# DS214SD.net
KiCad netlist of a schematic drawn in Altium Designer
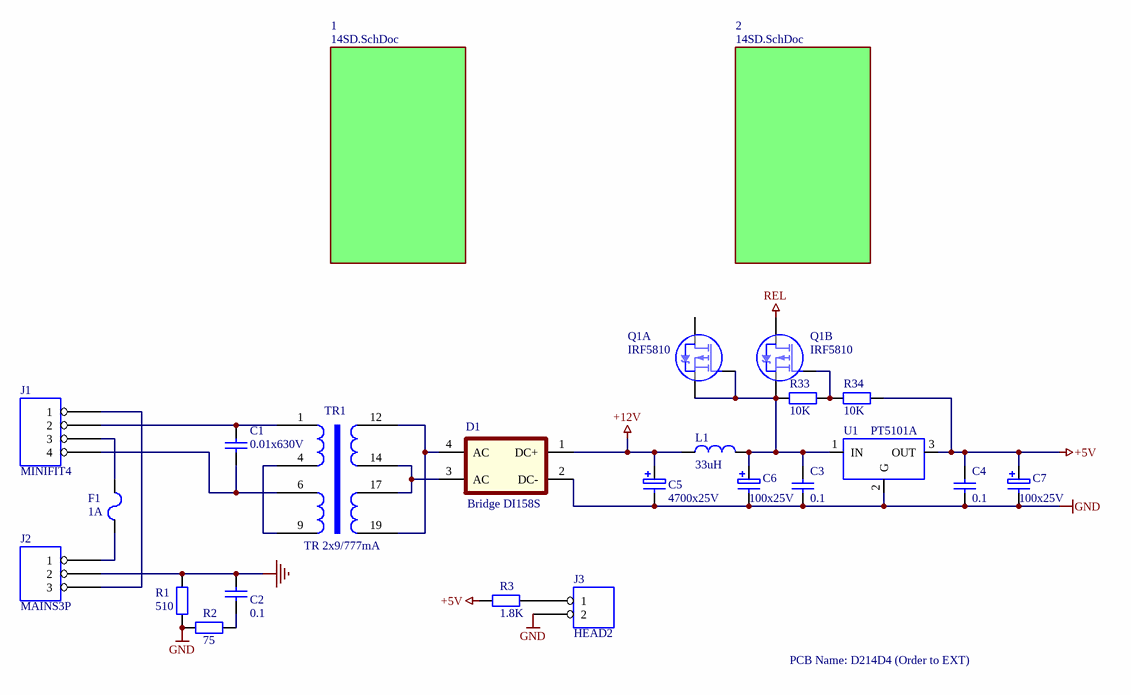
[diagram p0: DS214SD.SchDoc]

(export (version "E")
  (design (tool "Eeschema 10.0.6"))
  (components
    (comp (ref "C1")
      (value "0.01x630V")
      (footprint "C100N")
      (description "Capacitor")
      (fields (field (name "MANUFACTURER") "Generic Components") (field (name "PUBLISHER") "Altium Limited"))
      (libsource (lib "LES") (part "Cap"))
    )
    (comp (ref "C2")
      (value "0.1")
      (footprint "C0805")
      (description "Capacitor")
      (fields (field (name "MANUFACTURER") "Generic Components") (field (name "PUBLISHER") "Altium Limited"))
      (libsource (lib "LES") (part "Cap"))
    )
    (comp (ref "C3")
      (value "0.1")
      (footprint "C0805")
      (description "Capacitor")
      (fields (field (name "MANUFACTURER") "Generic Components") (field (name "PUBLISHER") "Altium Limited"))
      (libsource (lib "LES") (part "Cap"))
    )
    (comp (ref "C4")
      (value "0.1")
      (footprint "C0805")
      (description "Capacitor")
      (fields (field (name "MANUFACTURER") "Generic Components") (field (name "PUBLISHER") "Altium Limited"))
      (libsource (lib "LES") (part "Cap"))
    )
    (comp (ref "C5")
      (value "4700x25V")
      (footprint "CPOL75L")
      (description "Polarized Capacitor (Radial)")
      (fields (field (name "MANUFACTURER") "Generic Components") (field (name "PUBLISHER") "Altium Limited"))
      (libsource (lib "LES") (part "Cap Pol"))
    )
    (comp (ref "C6")
      (value "100x25V")
      (footprint "CPOL25")
      (description "Polarized Capacitor (Radial)")
      (fields (field (name "MANUFACTURER") "Generic Components") (field (name "PUBLISHER") "Altium Limited"))
      (libsource (lib "LES") (part "Cap Pol"))
    )
    (comp (ref "C7")
      (value "100x25V")
      (footprint "CPOL25")
      (description "Polarized Capacitor (Radial)")
      (fields (field (name "MANUFACTURER") "Generic Components") (field (name "PUBLISHER") "Altium Limited"))
      (libsource (lib "LES") (part "Cap Pol"))
    )
    (comp (ref "D1")
      (value "Bridge DI158S")
      (footprint "SDIP")
      (libsource (lib "LES") (part "Bridge DI158S"))
    )
    (comp (ref "F1")
      (value "1A")
      (footprint "FUSE")
      (description "Fuse")
      (libsource (lib "LES") (part "Fuse"))
    )
    (comp (ref "J1") (value "MINIFIT4") (footprint "MINIFIT4") (libsource (lib "LES") (part "HEAD4")))
    (comp (ref "J2") (value "MAINS3P") (footprint "MAINS3P") (libsource (lib "LES") (part "HEAD3")))
    (comp (ref "J3") (value "HEAD2") (footprint "2SIP100") (libsource (lib "LES") (part "HEAD2")))
    (comp (ref "L1") (value "33uH") (footprint "L050") (libsource (lib "LES") (part "INDUCTOR")))
    (comp (ref "Q1")
      (value "IRF5810")
      (footprint "TSOP6")
      (description "P-Channel MOSFET")
      (fields (field (name "PUBLISHER") "Altium Limited"))
      (libsource (lib "LES") (part "IRF5810"))
    )
    (comp (ref "R1")
      (value "510")
      (footprint "R0805")
      (description "Resistor")
      (fields (field (name "MANUFACTURER") "Generic Components") (field (name "PUBLISHER") "Altium Limited"))
      (libsource (lib "") (part "Res_1"))
    )
    (comp (ref "R2")
      (value "75")
      (footprint "R0805")
      (description "Resistor")
      (fields (field (name "MANUFACTURER") "Generic Components") (field (name "PUBLISHER") "Altium Limited"))
      (libsource (lib "LES") (part "Res"))
    )
    (comp (ref "R3")
      (value "1.8K")
      (footprint "R0805")
      (description "Resistor")
      (fields (field (name "MANUFACTURER") "Generic Components") (field (name "PUBLISHER") "Altium Limited"))
      (libsource (lib "LES") (part "Res"))
    )
    (comp (ref "R33")
      (value "10K")
      (footprint "R0805")
      (description "Resistor")
      (fields (field (name "MANUFACTURER") "Generic Components") (field (name "PUBLISHER") "Altium Limited"))
      (libsource (lib "LES") (part "Res"))
    )
    (comp (ref "R34")
      (value "10K")
      (footprint "R0805")
      (description "Resistor")
      (fields (field (name "MANUFACTURER") "Generic Components") (field (name "PUBLISHER") "Altium Limited"))
      (libsource (lib "LES") (part "Res"))
    )
    (comp (ref "TR1")
      (value "TR 2x9/777mA")
      (footprint "TR14VA")
      (libsource (lib "LES") (part "TR 2x9/777mA"))
    )
    (comp (ref "U1") (value "PT5101A") (footprint "PT5101A-LOW") (libsource (lib "LES") (part "PT5101A")))
  )
  (nets
    (net (code "1") (name "+5V") (class "Default")
      (node (ref "C4") (pin "2") (pinfunction "2_2") (pintype "passive"))
      (node (ref "C7") (pin "1") (pinfunction "1_1") (pintype "passive"))
      (node (ref "R3") (pin "1") (pinfunction "1_1") (pintype "passive"))
      (node (ref "R34") (pin "2") (pinfunction "2_2") (pintype "passive"))
      (node (ref "U1") (pin "3") (pinfunction "OUT_3") (pintype "passive"))
    )
    (net (code "2") (name "+12V") (class "Default")
      (node (ref "C5") (pin "1") (pinfunction "1_1") (pintype "passive"))
      (node (ref "D1") (pin "1") (pinfunction "DC+_1") (pintype "passive"))
      (node (ref "L1") (pin "1") (pinfunction "1_1") (pintype "passive"))
    )
    (net (code "3") (name "GND") (class "Default")
      (node (ref "C3") (pin "1") (pinfunction "1_1") (pintype "passive"))
      (node (ref "C4") (pin "1") (pinfunction "1_1") (pintype "passive"))
      (node (ref "C5") (pin "2") (pinfunction "2_2") (pintype "passive"))
      (node (ref "C6") (pin "2") (pinfunction "2_2") (pintype "passive"))
      (node (ref "C7") (pin "2") (pinfunction "2_2") (pintype "passive"))
      (node (ref "D1") (pin "2") (pinfunction "DC-_2") (pintype "passive"))
      (node (ref "J3") (pin "2") (pinfunction "2_2") (pintype "passive"))
      (node (ref "R1") (pin "1") (pinfunction "1_1") (pintype "passive"))
      (node (ref "R2") (pin "1") (pinfunction "1_1") (pintype "passive"))
      (node (ref "U1") (pin "2") (pinfunction "G_2") (pintype "passive"))
    )
    (net (code "4") (name "GNE") (class "Default")
      (node (ref "C2") (pin "2") (pinfunction "2_2") (pintype "passive"))
      (node (ref "J2") (pin "2") (pinfunction "2_2") (pintype "passive"))
      (node (ref "R1") (pin "2") (pinfunction "2_2") (pintype "passive"))
    )
    (net (code "5") (name "Net-(C1-Pad1)") (class "Default")
      (node (ref "C1") (pin "1") (pinfunction "1_1") (pintype "passive"))
      (node (ref "J1") (pin "4") (pinfunction "4_4") (pintype "passive"))
      (node (ref "TR1") (pin "6") (pinfunction "6_6") (pintype "passive"))
    )
    (net (code "6") (name "Net-(C1-Pad2)") (class "Default")
      (node (ref "C1") (pin "2") (pinfunction "2_2") (pintype "passive"))
      (node (ref "J1") (pin "2") (pinfunction "2_2") (pintype "passive"))
      (node (ref "TR1") (pin "1") (pinfunction "1_1") (pintype "passive"))
    )
    (net (code "7") (name "Net-(C2-Pad1)") (class "Default")
      (node (ref "C2") (pin "1") (pinfunction "1_1") (pintype "passive"))
      (node (ref "R2") (pin "2") (pinfunction "2_2") (pintype "passive"))
    )
    (net (code "8") (name "Net-(D1-AC-Pad3)") (class "Default")
      (node (ref "D1") (pin "3") (pinfunction "AC_3") (pintype "passive"))
      (node (ref "TR1") (pin "14") (pinfunction "14_14") (pintype "passive"))
      (node (ref "TR1") (pin "17") (pinfunction "17_17") (pintype "passive"))
    )
    (net (code "9") (name "Net-(D1-AC-Pad4)") (class "Default")
      (node (ref "D1") (pin "4") (pinfunction "AC_4") (pintype "passive"))
      (node (ref "TR1") (pin "12") (pinfunction "12_12") (pintype "passive"))
      (node (ref "TR1") (pin "19") (pinfunction "19_19") (pintype "passive"))
    )
    (net (code "10") (name "Net-(F1-Pad1)") (class "Default")
      (node (ref "F1") (pin "1") (pinfunction "1_1") (pintype "passive"))
      (node (ref "J2") (pin "1") (pinfunction "1_1") (pintype "passive"))
    )
    (net (code "11") (name "Net-(F1-Pad2)") (class "Default")
      (node (ref "F1") (pin "2") (pinfunction "2_2") (pintype "passive"))
      (node (ref "J1") (pin "3") (pinfunction "3_3") (pintype "passive"))
    )
    (net (code "12") (name "Net-(J1-Pad1)") (class "Default")
      (node (ref "J1") (pin "1") (pinfunction "1_1") (pintype "passive"))
      (node (ref "J2") (pin "3") (pinfunction "3_3") (pintype "passive"))
    )
    (net (code "13") (name "Net-(J3-Pad1)") (class "Default")
      (node (ref "J3") (pin "1") (pinfunction "1_1") (pintype "passive"))
      (node (ref "R3") (pin "2") (pinfunction "2_2") (pintype "passive"))
    )
    (net (code "14") (name "Net-(Q1A-G1)") (class "Default")
      (node (ref "C3") (pin "2") (pinfunction "2_2") (pintype "passive"))
      (node (ref "C6") (pin "1") (pinfunction "1_1") (pintype "passive"))
      (node (ref "L1") (pin "2") (pinfunction "2_2") (pintype "passive"))
      (node (ref "Q1") (pin "1") (pinfunction "G1_1") (pintype "passive"))
      (node (ref "Q1") (pin "2") (pinfunction "S2_2") (pintype "passive"))
      (node (ref "Q1") (pin "5") (pinfunction "S1_5") (pintype "passive"))
      (node (ref "R33") (pin "1") (pinfunction "1_1") (pintype "passive"))
      (node (ref "U1") (pin "1") (pinfunction "IN_1") (pintype "passive"))
    )
    (net (code "15") (name "Net-(Q1B-G2)") (class "Default")
      (node (ref "Q1") (pin "3") (pinfunction "G2_3") (pintype "passive"))
      (node (ref "R33") (pin "2") (pinfunction "2_2") (pintype "passive"))
      (node (ref "R34") (pin "1") (pinfunction "1_1") (pintype "passive"))
    )
    (net (code "16") (name "Net-(TR1-Pad4)") (class "Default")
      (node (ref "TR1") (pin "4") (pinfunction "4_4") (pintype "passive"))
      (node (ref "TR1") (pin "9") (pinfunction "9_9") (pintype "passive"))
    )
    (net (code "17") (name "REL") (class "Default")
      (node (ref "Q1") (pin "4") (pinfunction "D2_4") (pintype "passive"))
    )
    (net (code "18") (name "unconnected-(Q1A-D1-Pad6)") (class "Default")
      (node (ref "Q1") (pin "6") (pinfunction "D1_6") (pintype "passive"))
    )
  )
)
